# Power_Supply.net
KiCad netlist of a schematic drawn in Altium Designer
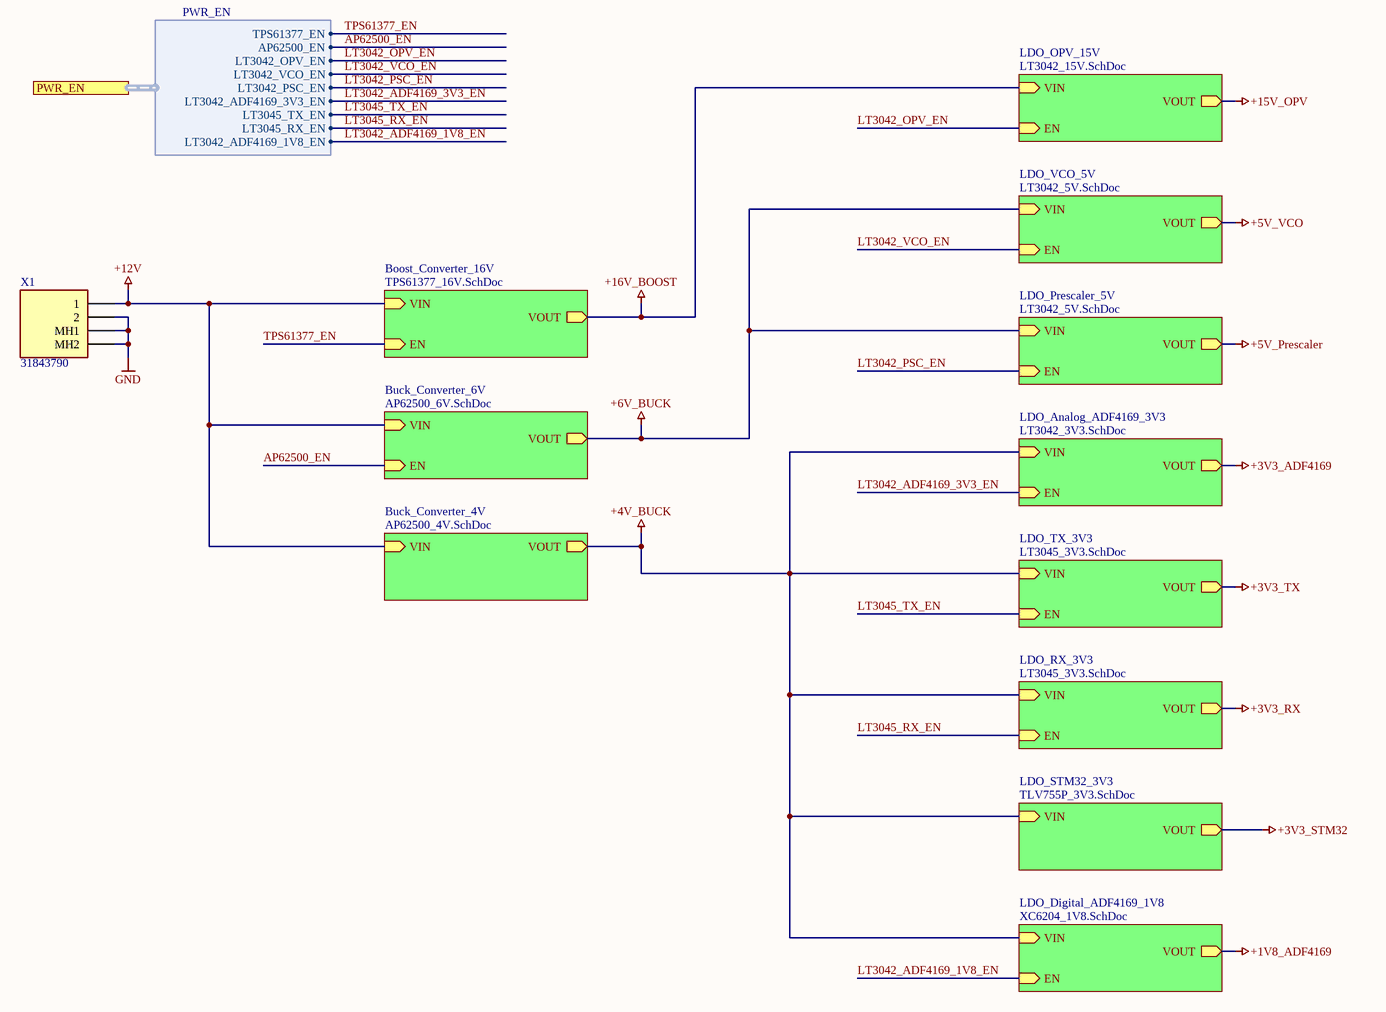
[diagram p0: Power_Supply.SchDoc]

(export (version "E")
  (design (tool "Eeschema 10.0.6"))
  (components
    (comp (ref "X1")
      (value "31843790")
      (footprint "31843790")
      (fields (field (name "MANUFACTURER") "Phoenix Contact"))
      (libsource (lib "database_library") (part "Connector_2Pin_2MH"))
    )
  )
  (nets
    (net (code "11") (name "+12V") (class "Default")
      (node (ref "X1") (pin "1") (pinfunction "1_1") (pintype "passive"))
    )
    (net (code "24") (name "GND") (class "Default")
      (node (ref "X1") (pin "2") (pinfunction "2_2") (pintype "passive"))
      (node (ref "X1") (pin "MH1") (pinfunction "MH1_MH1") (pintype "passive"))
      (node (ref "X1") (pin "MH2") (pinfunction "MH2_MH2") (pintype "passive"))
    )
  )
)
